# M112D.net
KiCad netlist of a schematic drawn in EAGLE
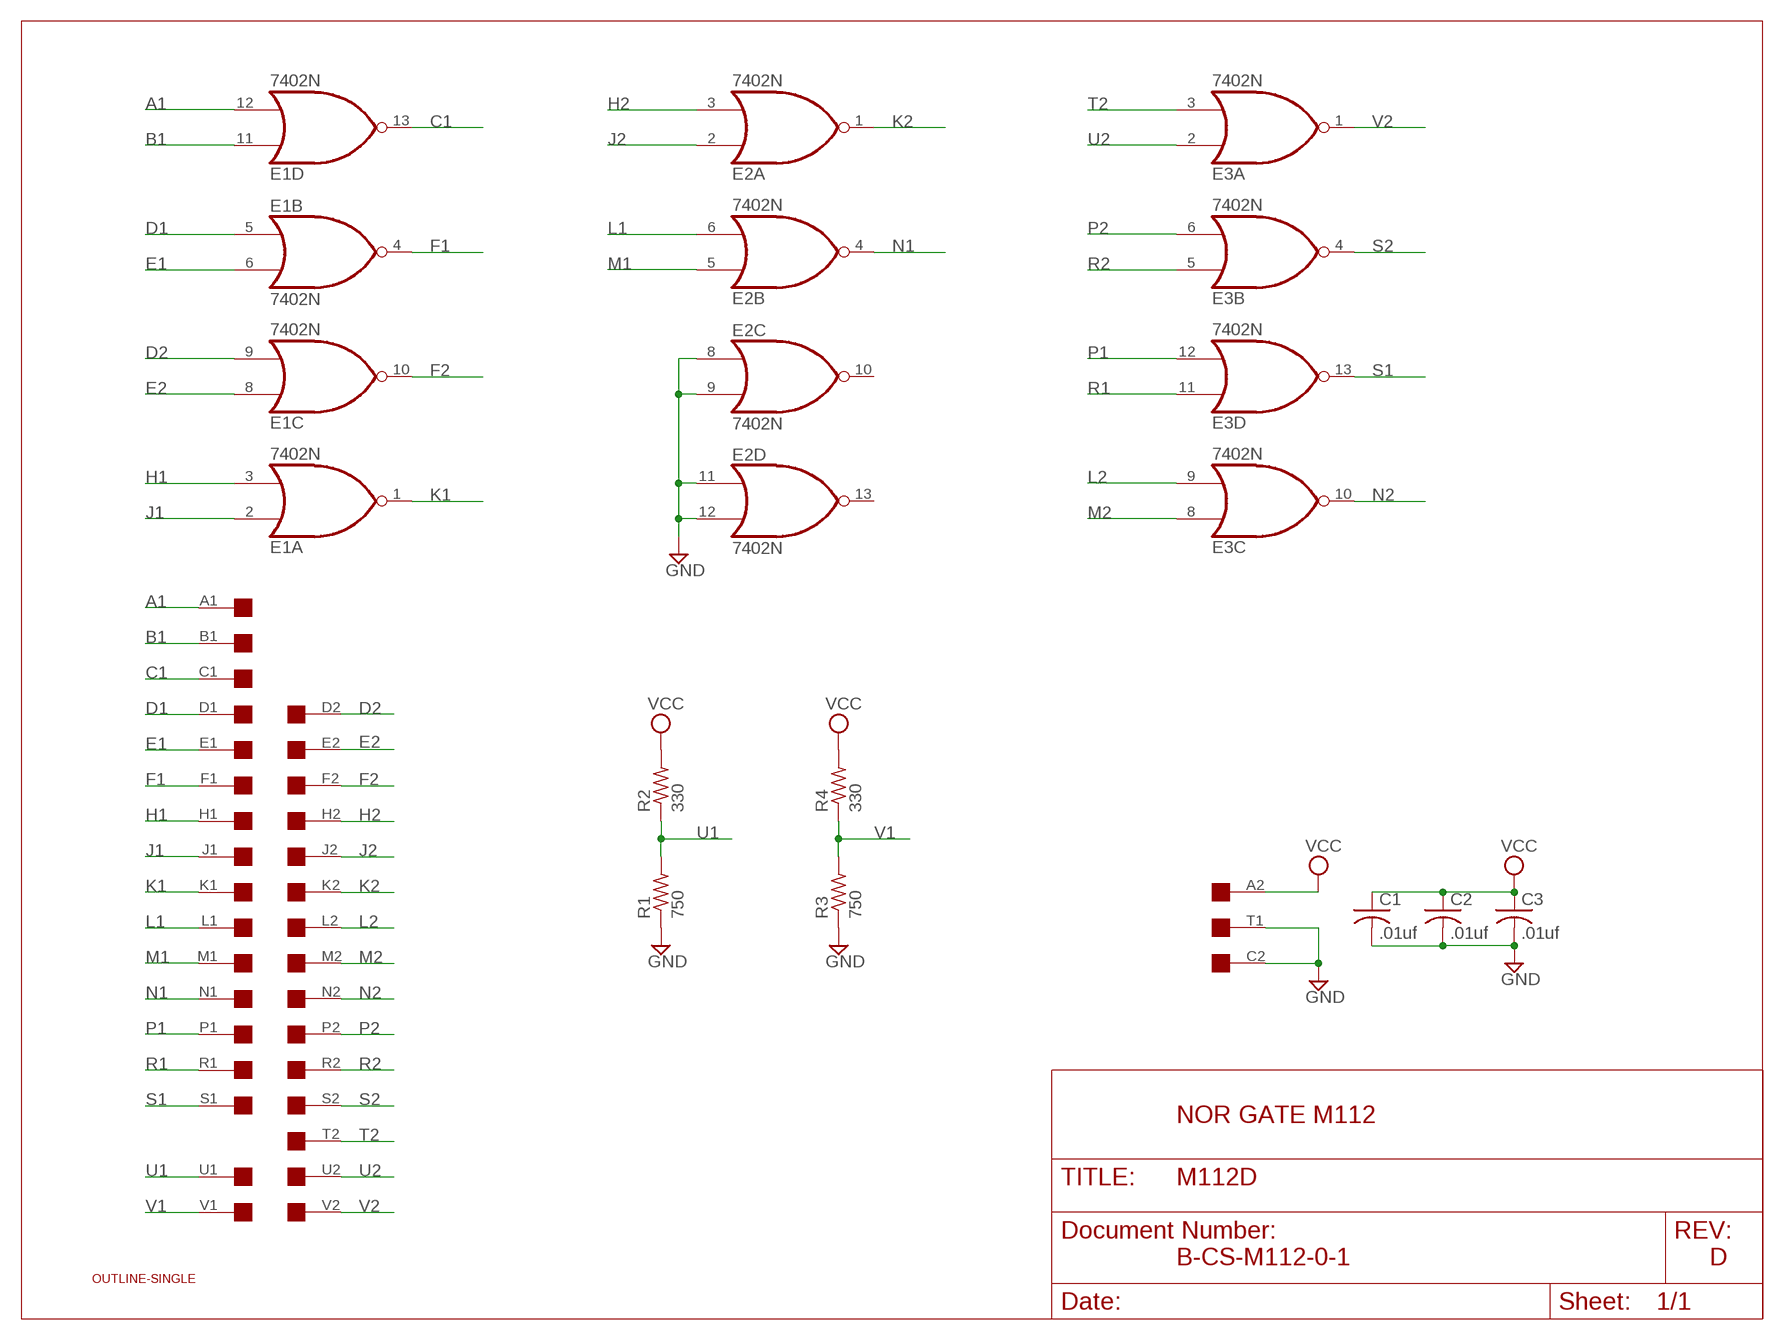
[diagram p0: schematic, sheet 1]

(export (version "E")
  (design (tool "Eeschema 10.0.6"))
  (components
    (comp (ref "C1")
      (value ".01uf")
      (footprint "eagle-import:C050-025X075")
      (libsource (lib "eagle-import") (part "C-US050-025X075"))
    )
    (comp (ref "C2")
      (value ".01uf")
      (footprint "eagle-import:C050-025X075")
      (libsource (lib "eagle-import") (part "C-US050-025X075"))
    )
    (comp (ref "C3")
      (value ".01uf")
      (footprint "eagle-import:C050-025X075")
      (libsource (lib "eagle-import") (part "C-US050-025X075"))
    )
    (comp (ref "E1")
      (value "7402N")
      (footprint "eagle-import:DIL14")
      (libsource (lib "eagle-import") (part "7402N"))
    )
    (comp (ref "E2")
      (value "7402N")
      (footprint "eagle-import:DIL14")
      (libsource (lib "eagle-import") (part "7402N"))
    )
    (comp (ref "E3")
      (value "7402N")
      (footprint "eagle-import:DIL14")
      (libsource (lib "eagle-import") (part "7402N"))
    )
    (comp (ref "R1")
      (value "750")
      (footprint "eagle-import:0207_10")
      (libsource (lib "eagle-import") (part "R-US_0207/10"))
    )
    (comp (ref "R2")
      (value "330")
      (footprint "eagle-import:0207_10")
      (libsource (lib "eagle-import") (part "R-US_0207/10"))
    )
    (comp (ref "R3")
      (value "750")
      (footprint "eagle-import:0207_10")
      (libsource (lib "eagle-import") (part "R-US_0207/10"))
    )
    (comp (ref "R4")
      (value "330")
      (footprint "eagle-import:0207_10")
      (libsource (lib "eagle-import") (part "R-US_0207/10"))
    )
    (comp (ref "U$1")
      (value "SINGLE")
      (footprint "eagle-import:EDGE-CON2")
      (libsource (lib "eagle-import") (part "SINGLE"))
    )
    (comp (ref "U$4")
      (value "OUTLINE-SINGLE")
      (footprint "eagle-import:SINGLE")
      (libsource (lib "eagle-import") (part "OUTLINE-SINGLE"))
    )
  )
  (nets
    (net (code "1") (name "/A1") (class "Default")
      (node (ref "E1") (pin "12") (pinfunction "I1_12") (pintype "input"))
      (node (ref "U$1") (pin "A1") (pinfunction "1_A1") (pintype "bidirectional"))
    )
    (net (code "2") (name "/B1") (class "Default")
      (node (ref "E1") (pin "11") (pinfunction "I0_11") (pintype "input"))
      (node (ref "U$1") (pin "B1") (pinfunction "1_B1") (pintype "bidirectional"))
    )
    (net (code "3") (name "/C1") (class "Default")
      (node (ref "E1") (pin "13") (pinfunction "O_13") (pintype "output"))
      (node (ref "U$1") (pin "C1") (pinfunction "1_C1") (pintype "bidirectional"))
    )
    (net (code "4") (name "/D1") (class "Default")
      (node (ref "E1") (pin "5") (pinfunction "I0_5") (pintype "input"))
      (node (ref "U$1") (pin "D1") (pinfunction "1_D1") (pintype "bidirectional"))
    )
    (net (code "5") (name "/D2") (class "Default")
      (node (ref "E1") (pin "9") (pinfunction "I1_9") (pintype "input"))
      (node (ref "U$1") (pin "D2") (pinfunction "1_D2") (pintype "bidirectional"))
    )
    (net (code "6") (name "/E1") (class "Default")
      (node (ref "E1") (pin "6") (pinfunction "I1_6") (pintype "input"))
      (node (ref "U$1") (pin "E1") (pinfunction "1_E1") (pintype "bidirectional"))
    )
    (net (code "7") (name "/E2") (class "Default")
      (node (ref "E1") (pin "8") (pinfunction "I0_8") (pintype "input"))
      (node (ref "U$1") (pin "E2") (pinfunction "1_E2") (pintype "bidirectional"))
    )
    (net (code "8") (name "/F1") (class "Default")
      (node (ref "E1") (pin "4") (pinfunction "O_4") (pintype "output"))
      (node (ref "U$1") (pin "F1") (pinfunction "1_F1") (pintype "bidirectional"))
    )
    (net (code "9") (name "/F2") (class "Default")
      (node (ref "E1") (pin "10") (pinfunction "O_10") (pintype "output"))
      (node (ref "U$1") (pin "F2") (pinfunction "1_F2") (pintype "bidirectional"))
    )
    (net (code "10") (name "/H1") (class "Default")
      (node (ref "E1") (pin "3") (pinfunction "I1_3") (pintype "input"))
      (node (ref "U$1") (pin "H1") (pinfunction "1_H1") (pintype "bidirectional"))
    )
    (net (code "11") (name "/H2") (class "Default")
      (node (ref "E2") (pin "3") (pinfunction "I1_3") (pintype "input"))
      (node (ref "U$1") (pin "H2") (pinfunction "1_H2") (pintype "bidirectional"))
    )
    (net (code "12") (name "/J1") (class "Default")
      (node (ref "E1") (pin "2") (pinfunction "I0_2") (pintype "input"))
      (node (ref "U$1") (pin "J1") (pinfunction "1_J1") (pintype "bidirectional"))
    )
    (net (code "13") (name "/J2") (class "Default")
      (node (ref "E2") (pin "2") (pinfunction "I0_2") (pintype "input"))
      (node (ref "U$1") (pin "J2") (pinfunction "1_J2") (pintype "bidirectional"))
    )
    (net (code "14") (name "/K1") (class "Default")
      (node (ref "E1") (pin "1") (pinfunction "O_1") (pintype "output"))
      (node (ref "U$1") (pin "K1") (pinfunction "1_K1") (pintype "bidirectional"))
    )
    (net (code "15") (name "/K2") (class "Default")
      (node (ref "E2") (pin "1") (pinfunction "O_1") (pintype "output"))
      (node (ref "U$1") (pin "K2") (pinfunction "1_K2") (pintype "bidirectional"))
    )
    (net (code "16") (name "/L1") (class "Default")
      (node (ref "E2") (pin "6") (pinfunction "I1_6") (pintype "input"))
      (node (ref "U$1") (pin "L1") (pinfunction "1_L1") (pintype "bidirectional"))
    )
    (net (code "17") (name "/L2") (class "Default")
      (node (ref "E3") (pin "9") (pinfunction "I1_9") (pintype "input"))
      (node (ref "U$1") (pin "L2") (pinfunction "1_L2") (pintype "bidirectional"))
    )
    (net (code "18") (name "/M1") (class "Default")
      (node (ref "E2") (pin "5") (pinfunction "I0_5") (pintype "input"))
      (node (ref "U$1") (pin "M1") (pinfunction "1_M1") (pintype "bidirectional"))
    )
    (net (code "19") (name "/M2") (class "Default")
      (node (ref "E3") (pin "8") (pinfunction "I0_8") (pintype "input"))
      (node (ref "U$1") (pin "M2") (pinfunction "1_M2") (pintype "bidirectional"))
    )
    (net (code "20") (name "/N1") (class "Default")
      (node (ref "E2") (pin "4") (pinfunction "O_4") (pintype "output"))
      (node (ref "U$1") (pin "N1") (pinfunction "1_N1") (pintype "bidirectional"))
    )
    (net (code "21") (name "/N2") (class "Default")
      (node (ref "E3") (pin "10") (pinfunction "O_10") (pintype "output"))
      (node (ref "U$1") (pin "N2") (pinfunction "1_N2") (pintype "bidirectional"))
    )
    (net (code "22") (name "/P1") (class "Default")
      (node (ref "E3") (pin "12") (pinfunction "I1_12") (pintype "input"))
      (node (ref "U$1") (pin "P1") (pinfunction "1_P1") (pintype "bidirectional"))
    )
    (net (code "23") (name "/P2") (class "Default")
      (node (ref "E3") (pin "6") (pinfunction "I1_6") (pintype "input"))
      (node (ref "U$1") (pin "P2") (pinfunction "1_P2") (pintype "bidirectional"))
    )
    (net (code "24") (name "/R1") (class "Default")
      (node (ref "E3") (pin "11") (pinfunction "I0_11") (pintype "input"))
      (node (ref "U$1") (pin "R1") (pinfunction "1_R1") (pintype "bidirectional"))
    )
    (net (code "25") (name "/R2") (class "Default")
      (node (ref "E3") (pin "5") (pinfunction "I0_5") (pintype "input"))
      (node (ref "U$1") (pin "R2") (pinfunction "1_R2") (pintype "bidirectional"))
    )
    (net (code "26") (name "/S1") (class "Default")
      (node (ref "E3") (pin "13") (pinfunction "O_13") (pintype "output"))
      (node (ref "U$1") (pin "S1") (pinfunction "1_S1") (pintype "bidirectional"))
    )
    (net (code "27") (name "/S2") (class "Default")
      (node (ref "E3") (pin "4") (pinfunction "O_4") (pintype "output"))
      (node (ref "U$1") (pin "S2") (pinfunction "1_S2") (pintype "bidirectional"))
    )
    (net (code "28") (name "/T2") (class "Default")
      (node (ref "E3") (pin "3") (pinfunction "I1_3") (pintype "input"))
      (node (ref "U$1") (pin "T2") (pinfunction "1_T2") (pintype "bidirectional"))
    )
    (net (code "29") (name "/U1") (class "Default")
      (node (ref "R1") (pin "2") (pinfunction "2_2") (pintype "passive"))
      (node (ref "R2") (pin "1") (pinfunction "1_1") (pintype "passive"))
      (node (ref "U$1") (pin "U1") (pinfunction "1_U1") (pintype "bidirectional"))
    )
    (net (code "30") (name "/U2") (class "Default")
      (node (ref "E3") (pin "2") (pinfunction "I0_2") (pintype "input"))
      (node (ref "U$1") (pin "U2") (pinfunction "1_U2") (pintype "bidirectional"))
    )
    (net (code "31") (name "/V1") (class "Default")
      (node (ref "R3") (pin "2") (pinfunction "2_2") (pintype "passive"))
      (node (ref "R4") (pin "1") (pinfunction "1_1") (pintype "passive"))
      (node (ref "U$1") (pin "V1") (pinfunction "1_V1") (pintype "bidirectional"))
    )
    (net (code "32") (name "/V2") (class "Default")
      (node (ref "E3") (pin "1") (pinfunction "O_1") (pintype "output"))
      (node (ref "U$1") (pin "V2") (pinfunction "1_V2") (pintype "bidirectional"))
    )
    (net (code "33") (name "GND") (class "Default")
      (node (ref "C1") (pin "2") (pinfunction "2_2") (pintype "passive"))
      (node (ref "C2") (pin "2") (pinfunction "2_2") (pintype "passive"))
      (node (ref "C3") (pin "2") (pinfunction "2_2") (pintype "passive"))
      (node (ref "E2") (pin "11") (pinfunction "I0_11") (pintype "input"))
      (node (ref "E2") (pin "12") (pinfunction "I1_12") (pintype "input"))
      (node (ref "E2") (pin "8") (pinfunction "I0_8") (pintype "input"))
      (node (ref "E2") (pin "9") (pinfunction "I1_9") (pintype "input"))
      (node (ref "R1") (pin "1") (pinfunction "1_1") (pintype "passive"))
      (node (ref "R3") (pin "1") (pinfunction "1_1") (pintype "passive"))
      (node (ref "U$1") (pin "C2") (pinfunction "1_C2") (pintype "bidirectional"))
      (node (ref "U$1") (pin "T1") (pinfunction "1_T1") (pintype "bidirectional"))
    )
    (net (code "34") (name "VCC") (class "Default")
      (node (ref "C1") (pin "1") (pinfunction "1_1") (pintype "passive"))
      (node (ref "C2") (pin "1") (pinfunction "1_1") (pintype "passive"))
      (node (ref "C3") (pin "1") (pinfunction "1_1") (pintype "passive"))
      (node (ref "R2") (pin "2") (pinfunction "2_2") (pintype "passive"))
      (node (ref "R4") (pin "2") (pinfunction "2_2") (pintype "passive"))
      (node (ref "U$1") (pin "A2") (pinfunction "1_A2") (pintype "bidirectional"))
    )
    (net (code "35") (name "unconnected-(E2C-O-Pad10)") (class "Default")
      (node (ref "E2") (pin "10") (pinfunction "O_10") (pintype "output"))
    )
    (net (code "36") (name "unconnected-(E2D-O-Pad13)") (class "Default")
      (node (ref "E2") (pin "13") (pinfunction "O_13") (pintype "output"))
    )
  )
)
